# PB-to-PTS.net
KiCad netlist of a schematic drawn in EAGLE
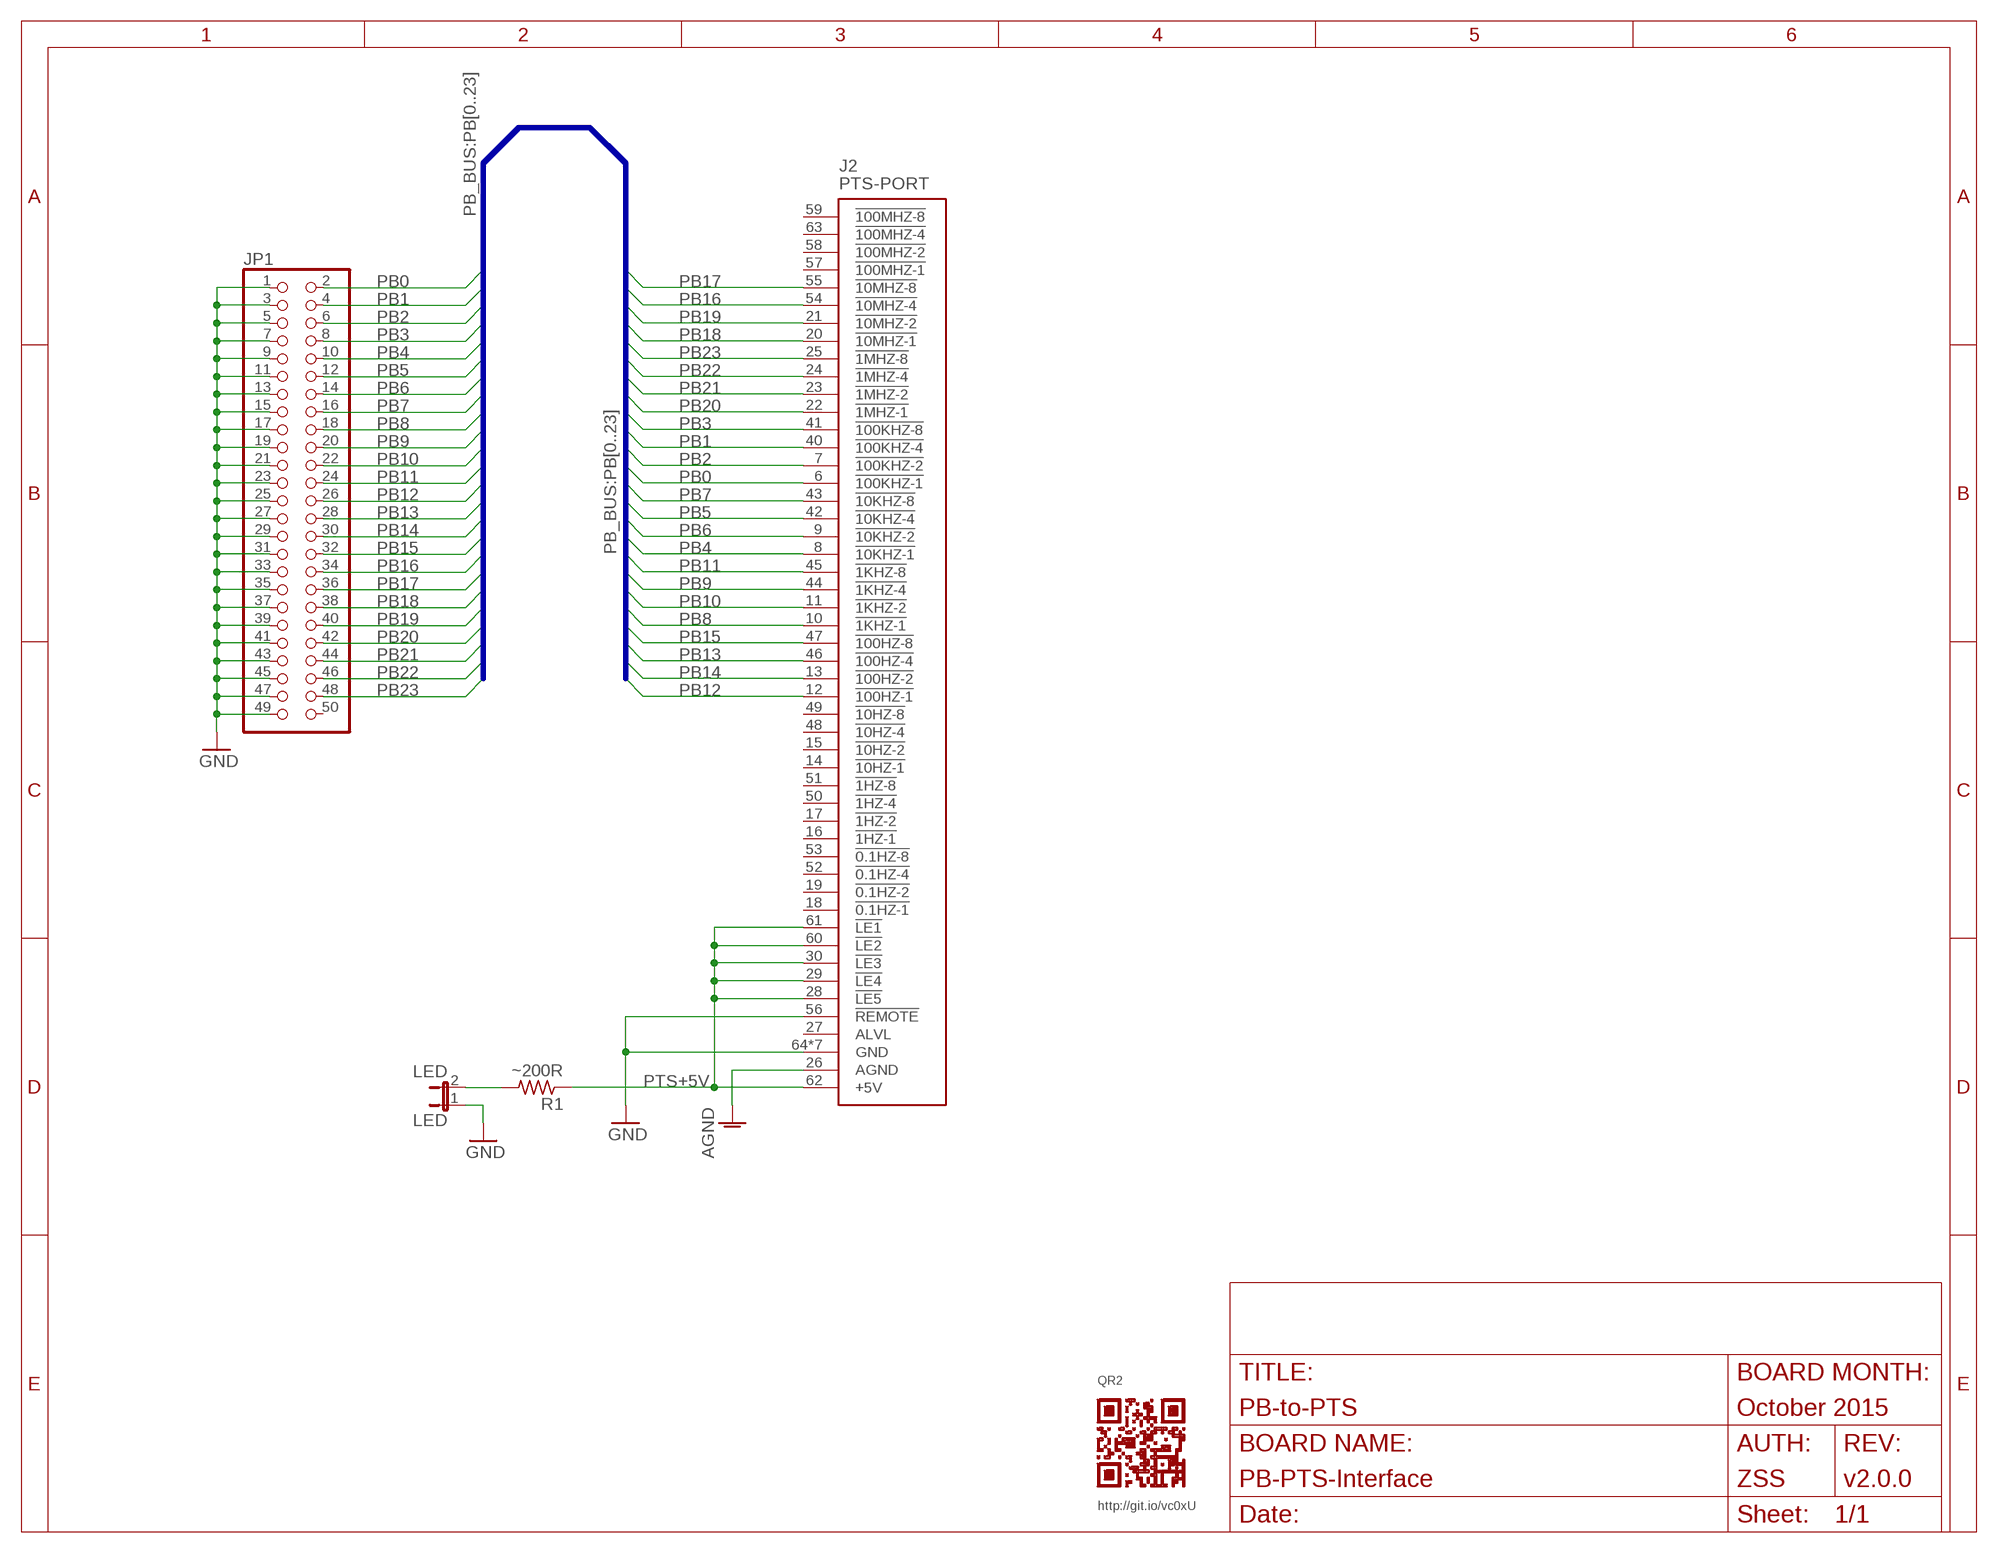
[diagram p0: schematic, sheet 1]

(export (version "E")
  (design (tool "Eeschema 10.0.6"))
  (components
    (comp (ref "J2")
      (value "PTS-PORT")
      (footprint "eagle-import:MOLEX-73776-0201")
      (libsource (lib "eagle-import") (part "PTS-PORT"))
    )
    (comp (ref "JP1")
      (value "PINHD-2X25")
      (footprint "eagle-import:2X25")
      (libsource (lib "eagle-import") (part "PINHD-2X25"))
    )
    (comp (ref "LED")
      (value "LED")
      (footprint "eagle-import:JP1")
      (libsource (lib "eagle-import") (part "JP1E"))
    )
    (comp (ref "QR2")
      (value "QR-HTTP://GIT.IO/VC0XU")
      (footprint "eagle-import:QR-HTTP___GIT.IO_VC0XU")
      (libsource (lib "eagle-import") (part "QR-HTTP{colon}//GIT.IO/VC0XU"))
    )
    (comp (ref "R1")
      (value "~200R")
      (footprint "eagle-import:R0805")
      (libsource (lib "eagle-import") (part "R-US_R0805"))
    )
  )
  (nets
    (net (code "25") (name "/PB0") (class "Default")
      (node (ref "J2") (pin "6") (pinfunction "~{100KHZ-1}_6") (pintype "input"))
      (node (ref "JP1") (pin "2") (pinfunction "2_2") (pintype "passive"))
    )
    (net (code "26") (name "/PB1") (class "Default")
      (node (ref "J2") (pin "40") (pinfunction "~{100KHZ-4}_40") (pintype "input"))
      (node (ref "JP1") (pin "4") (pinfunction "4_4") (pintype "passive"))
    )
    (net (code "27") (name "/PB2") (class "Default")
      (node (ref "J2") (pin "7") (pinfunction "~{100KHZ-2}_7") (pintype "input"))
      (node (ref "JP1") (pin "6") (pinfunction "6_6") (pintype "passive"))
    )
    (net (code "28") (name "/PB3") (class "Default")
      (node (ref "J2") (pin "41") (pinfunction "~{100KHZ-8}_41") (pintype "input"))
      (node (ref "JP1") (pin "8") (pinfunction "8_8") (pintype "passive"))
    )
    (net (code "29") (name "/PB4") (class "Default")
      (node (ref "J2") (pin "8") (pinfunction "~{10KHZ-1}_8") (pintype "input"))
      (node (ref "JP1") (pin "10") (pinfunction "10_10") (pintype "passive"))
    )
    (net (code "30") (name "/PB5") (class "Default")
      (node (ref "J2") (pin "42") (pinfunction "~{10KHZ-4}_42") (pintype "input"))
      (node (ref "JP1") (pin "12") (pinfunction "12_12") (pintype "passive"))
    )
    (net (code "31") (name "/PB6") (class "Default")
      (node (ref "J2") (pin "9") (pinfunction "~{10KHZ-2}_9") (pintype "input"))
      (node (ref "JP1") (pin "14") (pinfunction "14_14") (pintype "passive"))
    )
    (net (code "32") (name "/PB7") (class "Default")
      (node (ref "J2") (pin "43") (pinfunction "~{10KHZ-8}_43") (pintype "input"))
      (node (ref "JP1") (pin "16") (pinfunction "16_16") (pintype "passive"))
    )
    (net (code "33") (name "/PB8") (class "Default")
      (node (ref "J2") (pin "10") (pinfunction "~{1KHZ-1}_10") (pintype "input"))
      (node (ref "JP1") (pin "18") (pinfunction "18_18") (pintype "passive"))
    )
    (net (code "34") (name "/PB9") (class "Default")
      (node (ref "J2") (pin "44") (pinfunction "~{1KHZ-4}_44") (pintype "input"))
      (node (ref "JP1") (pin "20") (pinfunction "20_20") (pintype "passive"))
    )
    (net (code "35") (name "/PB10") (class "Default")
      (node (ref "J2") (pin "11") (pinfunction "~{1KHZ-2}_11") (pintype "input"))
      (node (ref "JP1") (pin "22") (pinfunction "22_22") (pintype "passive"))
    )
    (net (code "36") (name "/PB11") (class "Default")
      (node (ref "J2") (pin "45") (pinfunction "~{1KHZ-8}_45") (pintype "input"))
      (node (ref "JP1") (pin "24") (pinfunction "24_24") (pintype "passive"))
    )
    (net (code "37") (name "/PB12") (class "Default")
      (node (ref "J2") (pin "12") (pinfunction "~{100HZ-1}_12") (pintype "input"))
      (node (ref "JP1") (pin "26") (pinfunction "26_26") (pintype "passive"))
    )
    (net (code "38") (name "/PB13") (class "Default")
      (node (ref "J2") (pin "46") (pinfunction "~{100HZ-4}_46") (pintype "input"))
      (node (ref "JP1") (pin "28") (pinfunction "28_28") (pintype "passive"))
    )
    (net (code "39") (name "/PB14") (class "Default")
      (node (ref "J2") (pin "13") (pinfunction "~{100HZ-2}_13") (pintype "input"))
      (node (ref "JP1") (pin "30") (pinfunction "30_30") (pintype "passive"))
    )
    (net (code "40") (name "/PB15") (class "Default")
      (node (ref "J2") (pin "47") (pinfunction "~{100HZ-8}_47") (pintype "input"))
      (node (ref "JP1") (pin "32") (pinfunction "32_32") (pintype "passive"))
    )
    (net (code "41") (name "/PB16") (class "Default")
      (node (ref "J2") (pin "54") (pinfunction "~{10MHZ-4}_54") (pintype "input"))
      (node (ref "JP1") (pin "34") (pinfunction "34_34") (pintype "passive"))
    )
    (net (code "42") (name "/PB17") (class "Default")
      (node (ref "J2") (pin "55") (pinfunction "~{10MHZ-8}_55") (pintype "input"))
      (node (ref "JP1") (pin "36") (pinfunction "36_36") (pintype "passive"))
    )
    (net (code "43") (name "/PB18") (class "Default")
      (node (ref "J2") (pin "20") (pinfunction "~{10MHZ-1}_20") (pintype "input"))
      (node (ref "JP1") (pin "38") (pinfunction "38_38") (pintype "passive"))
    )
    (net (code "44") (name "/PB19") (class "Default")
      (node (ref "J2") (pin "21") (pinfunction "~{10MHZ-2}_21") (pintype "input"))
      (node (ref "JP1") (pin "40") (pinfunction "40_40") (pintype "passive"))
    )
    (net (code "45") (name "/PB20") (class "Default")
      (node (ref "J2") (pin "22") (pinfunction "~{1MHZ-1}_22") (pintype "input"))
      (node (ref "JP1") (pin "42") (pinfunction "42_42") (pintype "passive"))
    )
    (net (code "46") (name "/PB21") (class "Default")
      (node (ref "J2") (pin "23") (pinfunction "~{1MHZ-2}_23") (pintype "input"))
      (node (ref "JP1") (pin "44") (pinfunction "44_44") (pintype "passive"))
    )
    (net (code "47") (name "/PB22") (class "Default")
      (node (ref "J2") (pin "24") (pinfunction "~{1MHZ-4}_24") (pintype "input"))
      (node (ref "JP1") (pin "46") (pinfunction "46_46") (pintype "passive"))
    )
    (net (code "48") (name "/PB23") (class "Default")
      (node (ref "J2") (pin "25") (pinfunction "~{1MHZ-8}_25") (pintype "input"))
      (node (ref "JP1") (pin "48") (pinfunction "48_48") (pintype "passive"))
    )
    (net (code "50") (name "/PTS+5V") (class "Default")
      (node (ref "J2") (pin "28") (pinfunction "~{LE5}_28") (pintype "input"))
      (node (ref "J2") (pin "29") (pinfunction "~{LE4}_29") (pintype "input"))
      (node (ref "J2") (pin "30") (pinfunction "~{LE3}_30") (pintype "input"))
      (node (ref "J2") (pin "60") (pinfunction "~{LE2}_60") (pintype "input"))
      (node (ref "J2") (pin "61") (pinfunction "~{LE1}_61") (pintype "input"))
      (node (ref "J2") (pin "62") (pinfunction "+5V_62") (pintype "bidirectional"))
      (node (ref "R1") (pin "1") (pinfunction "1_1") (pintype "passive"))
    )
    (net (code "51") (name "AGND") (class "Default")
      (node (ref "J2") (pin "26") (pinfunction "AGND_26") (pintype "power_in"))
    )
    (net (code "52") (name "GND") (class "Default")
      (node (ref "J2") (pin "56") (pinfunction "~{REMOTE}_56") (pintype "input"))
      (node (ref "J2") (pin "64") (pinfunction "GND_64") (pintype "power_in"))
      (node (ref "J2") (pin "SHIELD1") (pinfunction "GND_SHIELD1") (pintype "power_in"))
      (node (ref "J2") (pin "SHIELD2") (pinfunction "GND_SHIELD2") (pintype "power_in"))
      (node (ref "J2") (pin "SHIELD3") (pinfunction "GND_SHIELD3") (pintype "power_in"))
      (node (ref "J2") (pin "SHIELD4") (pinfunction "GND_SHIELD4") (pintype "power_in"))
      (node (ref "J2") (pin "SHIELD5") (pinfunction "GND_SHIELD5") (pintype "power_in"))
      (node (ref "J2") (pin "SHIELD6") (pinfunction "GND_SHIELD6") (pintype "power_in"))
      (node (ref "JP1") (pin "1") (pinfunction "1_1") (pintype "passive"))
      (node (ref "JP1") (pin "11") (pinfunction "11_11") (pintype "passive"))
      (node (ref "JP1") (pin "13") (pinfunction "13_13") (pintype "passive"))
      (node (ref "JP1") (pin "15") (pinfunction "15_15") (pintype "passive"))
      (node (ref "JP1") (pin "17") (pinfunction "17_17") (pintype "passive"))
      (node (ref "JP1") (pin "19") (pinfunction "19_19") (pintype "passive"))
      (node (ref "JP1") (pin "21") (pinfunction "21_21") (pintype "passive"))
      (node (ref "JP1") (pin "23") (pinfunction "23_23") (pintype "passive"))
      (node (ref "JP1") (pin "25") (pinfunction "25_25") (pintype "passive"))
      (node (ref "JP1") (pin "27") (pinfunction "27_27") (pintype "passive"))
      (node (ref "JP1") (pin "29") (pinfunction "29_29") (pintype "passive"))
      (node (ref "JP1") (pin "3") (pinfunction "3_3") (pintype "passive"))
      (node (ref "JP1") (pin "31") (pinfunction "31_31") (pintype "passive"))
      (node (ref "JP1") (pin "33") (pinfunction "33_33") (pintype "passive"))
      (node (ref "JP1") (pin "35") (pinfunction "35_35") (pintype "passive"))
      (node (ref "JP1") (pin "37") (pinfunction "37_37") (pintype "passive"))
      (node (ref "JP1") (pin "39") (pinfunction "39_39") (pintype "passive"))
      (node (ref "JP1") (pin "41") (pinfunction "41_41") (pintype "passive"))
      (node (ref "JP1") (pin "43") (pinfunction "43_43") (pintype "passive"))
      (node (ref "JP1") (pin "45") (pinfunction "45_45") (pintype "passive"))
      (node (ref "JP1") (pin "47") (pinfunction "47_47") (pintype "passive"))
      (node (ref "JP1") (pin "49") (pinfunction "49_49") (pintype "passive"))
      (node (ref "JP1") (pin "5") (pinfunction "5_5") (pintype "passive"))
      (node (ref "JP1") (pin "7") (pinfunction "7_7") (pintype "passive"))
      (node (ref "JP1") (pin "9") (pinfunction "9_9") (pintype "passive"))
      (node (ref "LED") (pin "1") (pinfunction "1_1") (pintype "passive"))
    )
    (net (code "53") (name "Net-(LED-Pad2)") (class "Default")
      (node (ref "LED") (pin "2") (pinfunction "2_2") (pintype "passive"))
      (node (ref "R1") (pin "2") (pinfunction "2_2") (pintype "passive"))
    )
    (net (code "54") (name "unconnected-(J2-ALVL-Pad27)") (class "Default")
      (node (ref "J2") (pin "27") (pinfunction "ALVL_27") (pintype "input"))
    )
    (net (code "55") (name "unconnected-(J2-~{0.1HZ-1}-Pad18)") (class "Default")
      (node (ref "J2") (pin "18") (pinfunction "~{0.1HZ-1}_18") (pintype "input"))
    )
    (net (code "56") (name "unconnected-(J2-~{0.1HZ-2}-Pad19)") (class "Default")
      (node (ref "J2") (pin "19") (pinfunction "~{0.1HZ-2}_19") (pintype "input"))
    )
    (net (code "57") (name "unconnected-(J2-~{0.1HZ-4}-Pad52)") (class "Default")
      (node (ref "J2") (pin "52") (pinfunction "~{0.1HZ-4}_52") (pintype "input"))
    )
    (net (code "58") (name "unconnected-(J2-~{0.1HZ-8}-Pad53)") (class "Default")
      (node (ref "J2") (pin "53") (pinfunction "~{0.1HZ-8}_53") (pintype "input"))
    )
    (net (code "59") (name "unconnected-(J2-~{1HZ-1}-Pad16)") (class "Default")
      (node (ref "J2") (pin "16") (pinfunction "~{1HZ-1}_16") (pintype "input"))
    )
    (net (code "60") (name "unconnected-(J2-~{1HZ-2}-Pad17)") (class "Default")
      (node (ref "J2") (pin "17") (pinfunction "~{1HZ-2}_17") (pintype "input"))
    )
    (net (code "61") (name "unconnected-(J2-~{1HZ-4}-Pad50)") (class "Default")
      (node (ref "J2") (pin "50") (pinfunction "~{1HZ-4}_50") (pintype "input"))
    )
    (net (code "62") (name "unconnected-(J2-~{1HZ-8}-Pad51)") (class "Default")
      (node (ref "J2") (pin "51") (pinfunction "~{1HZ-8}_51") (pintype "input"))
    )
    (net (code "63") (name "unconnected-(J2-~{10HZ-1}-Pad14)") (class "Default")
      (node (ref "J2") (pin "14") (pinfunction "~{10HZ-1}_14") (pintype "input"))
    )
    (net (code "64") (name "unconnected-(J2-~{10HZ-2}-Pad15)") (class "Default")
      (node (ref "J2") (pin "15") (pinfunction "~{10HZ-2}_15") (pintype "input"))
    )
    (net (code "65") (name "unconnected-(J2-~{10HZ-4}-Pad48)") (class "Default")
      (node (ref "J2") (pin "48") (pinfunction "~{10HZ-4}_48") (pintype "input"))
    )
    (net (code "66") (name "unconnected-(J2-~{10HZ-8}-Pad49)") (class "Default")
      (node (ref "J2") (pin "49") (pinfunction "~{10HZ-8}_49") (pintype "input"))
    )
    (net (code "67") (name "unconnected-(J2-~{100MHZ-1}-Pad57)") (class "Default")
      (node (ref "J2") (pin "57") (pinfunction "~{100MHZ-1}_57") (pintype "input"))
    )
    (net (code "68") (name "unconnected-(J2-~{100MHZ-2}-Pad58)") (class "Default")
      (node (ref "J2") (pin "58") (pinfunction "~{100MHZ-2}_58") (pintype "input"))
    )
    (net (code "69") (name "unconnected-(J2-~{100MHZ-4}-Pad63)") (class "Default")
      (node (ref "J2") (pin "63") (pinfunction "~{100MHZ-4}_63") (pintype "input"))
    )
    (net (code "70") (name "unconnected-(J2-~{100MHZ-8}-Pad59)") (class "Default")
      (node (ref "J2") (pin "59") (pinfunction "~{100MHZ-8}_59") (pintype "input"))
    )
    (net (code "71") (name "unconnected-(JP1-Pad50)") (class "Default")
      (node (ref "JP1") (pin "50") (pinfunction "50_50") (pintype "passive"))
    )
  )
)
